# BOOST-IR.net
KiCad netlist of a schematic drawn in EAGLE
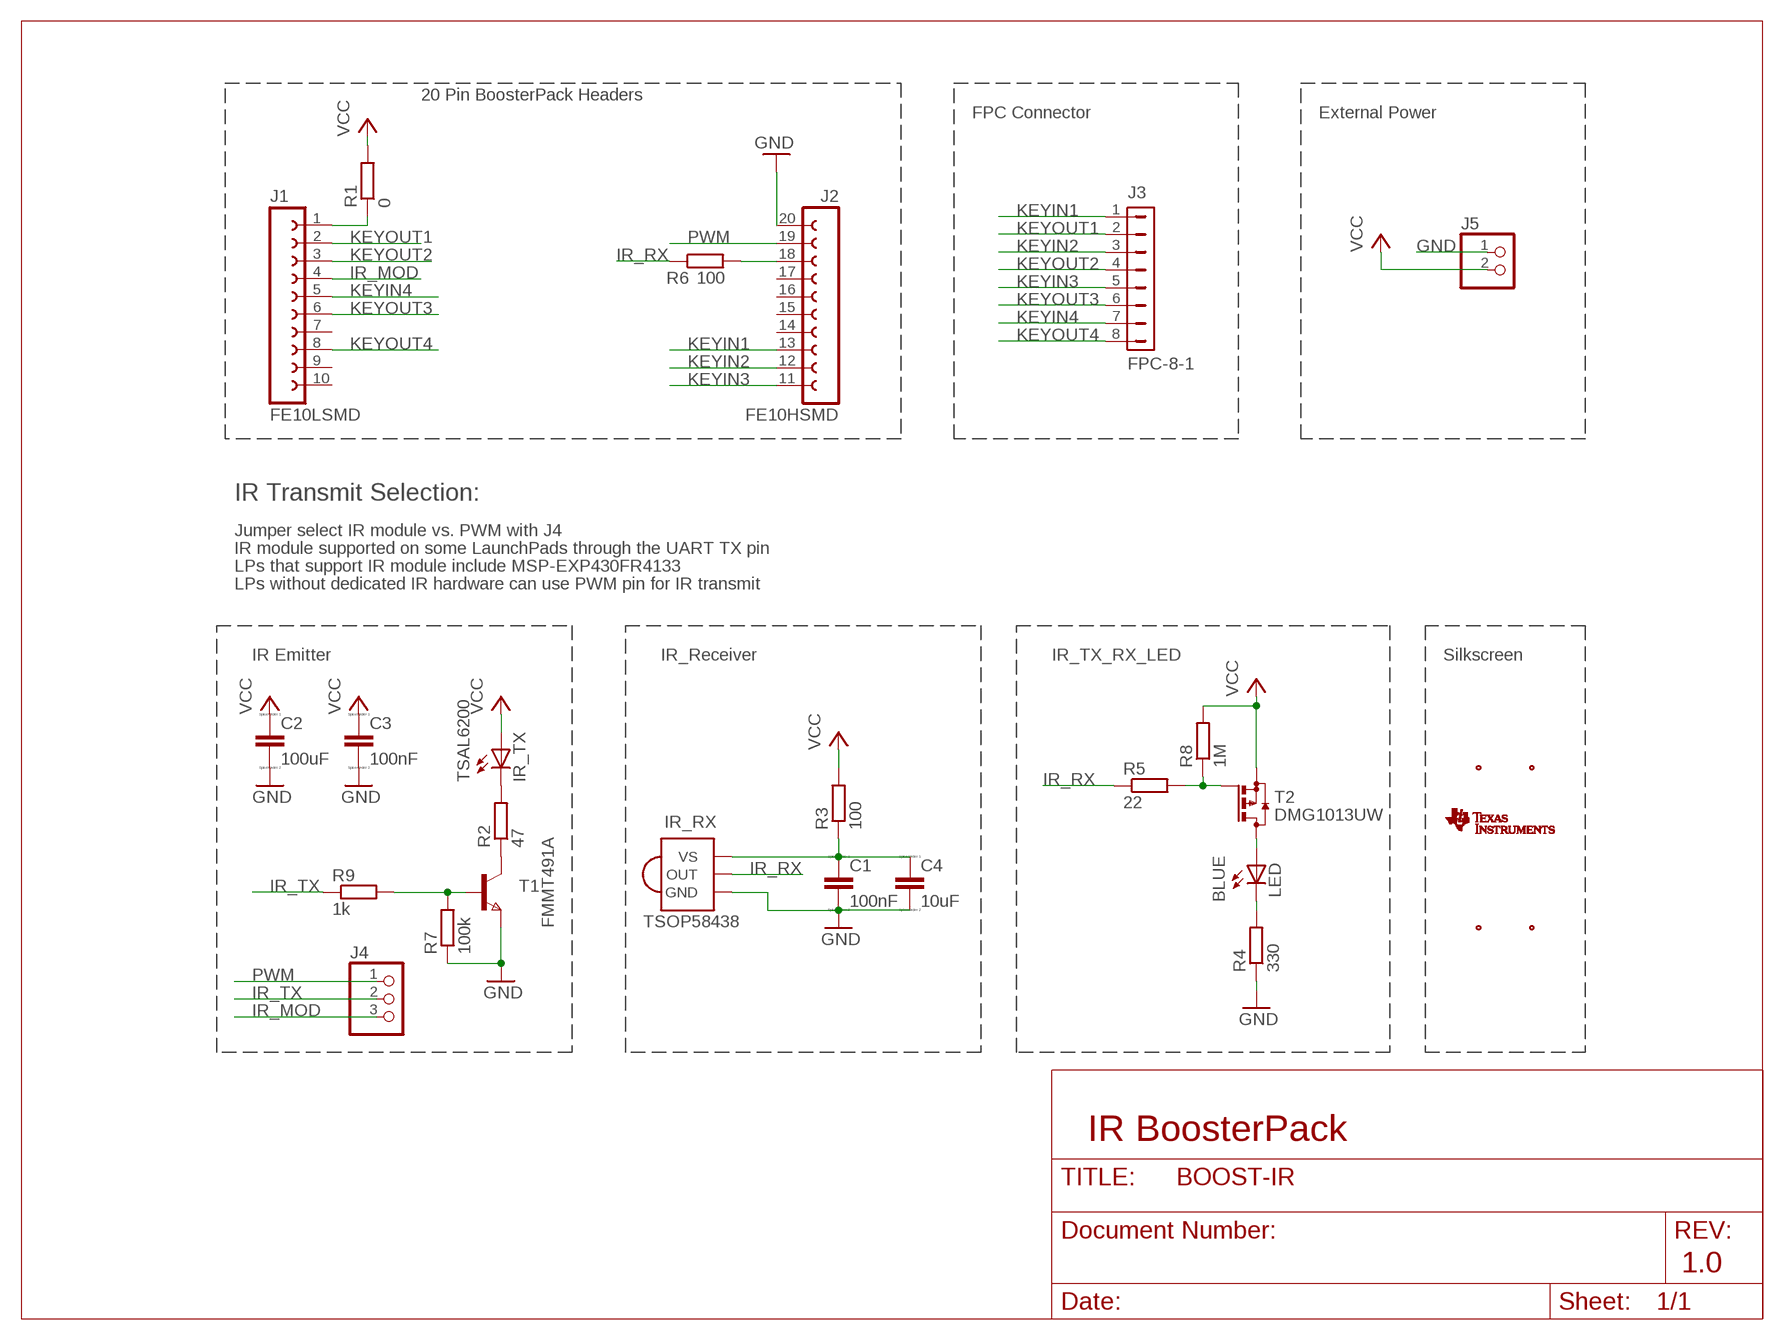
[diagram p0: schematic, sheet 1]

(export (version "E")
  (design (tool "Eeschema 10.0.6"))
  (components
    (comp (ref "C1")
      (value "100nF")
      (footprint "eagle-import:C0603")
      (libsource (lib "eagle-import") (part "CC0603"))
    )
    (comp (ref "C2")
      (value "100uF")
      (footprint "eagle-import:C1206")
      (libsource (lib "eagle-import") (part "CC1206"))
    )
    (comp (ref "C3")
      (value "100nF")
      (footprint "eagle-import:C0603")
      (libsource (lib "eagle-import") (part "CC0603"))
    )
    (comp (ref "C4")
      (value "10uF")
      (footprint "eagle-import:C0805")
      (libsource (lib "eagle-import") (part "C"))
    )
    (comp (ref "IR_RX")
      (value "TSOP58438")
      (footprint "eagle-import:TSOP58438")
      (libsource (lib "eagle-import") (part "TSOP58438"))
    )
    (comp (ref "IR_TX")
      (value "TSAL6200")
      (footprint "eagle-import:IR_LED_PAC")
      (libsource (lib "eagle-import") (part "IR_LED"))
    )
    (comp (ref "J1")
      (value "FE10LSMD")
      (footprint "eagle-import:FE10SMD")
      (libsource (lib "eagle-import") (part "FE10LSMD"))
    )
    (comp (ref "J2")
      (value "FE10HSMD")
      (footprint "eagle-import:FE10HSMD")
      (libsource (lib "eagle-import") (part "FE10HSMD"))
    )
    (comp (ref "J3")
      (value "FPC-8-1")
      (footprint "eagle-import:FPC_IR")
      (libsource (lib "eagle-import") (part "FPC_BP"))
    )
    (comp (ref "J4")
      (value "PINHD1X3")
      (footprint "eagle-import:1X03")
      (libsource (lib "eagle-import") (part "PINHD1X3"))
    )
    (comp (ref "J5")
      (value "HEADER1X2")
      (footprint "eagle-import:HEADER1X2")
      (libsource (lib "eagle-import") (part "HEADER1X2"))
    )
    (comp (ref "LED")
      (value "BLUE")
      (footprint "eagle-import:CHIPLED_0603")
      (libsource (lib "eagle-import") (part "LEDCHIPLED_0603"))
    )
    (comp (ref "R1")
      (value "0")
      (footprint "eagle-import:R1206")
      (libsource (lib "eagle-import") (part "R-EU_R1206"))
    )
    (comp (ref "R2")
      (value "47")
      (footprint "eagle-import:R1206")
      (libsource (lib "eagle-import") (part "R-EU_R1206"))
    )
    (comp (ref "R3")
      (value "100")
      (footprint "eagle-import:R0603")
      (libsource (lib "eagle-import") (part "R-EU_R0603"))
    )
    (comp (ref "R4")
      (value "330")
      (footprint "eagle-import:R0603")
      (libsource (lib "eagle-import") (part "R-EU_R0603"))
    )
    (comp (ref "R5")
      (value "22")
      (footprint "eagle-import:R0603")
      (libsource (lib "eagle-import") (part "R-EU_R0603"))
    )
    (comp (ref "R6")
      (value "100")
      (footprint "eagle-import:R0603")
      (libsource (lib "eagle-import") (part "R-EU_R0603"))
    )
    (comp (ref "R7")
      (value "100k")
      (footprint "eagle-import:R0603")
      (libsource (lib "eagle-import") (part "R-EU_R0603"))
    )
    (comp (ref "R8")
      (value "1M")
      (footprint "eagle-import:R0603")
      (libsource (lib "eagle-import") (part "R-EU_R0603"))
    )
    (comp (ref "R9")
      (value "1k")
      (footprint "eagle-import:R0603")
      (libsource (lib "eagle-import") (part "R-EU_R0603"))
    )
    (comp (ref "T1")
      (value "FMMT491A")
      (footprint "eagle-import:SOT-23")
      (fields (field (name "MPN") "DSS20201L-7"))
      (libsource (lib "eagle-import") (part "NPNSOT23"))
    )
    (comp (ref "T2")
      (value "DMG1013UW")
      (footprint "eagle-import:SOT323")
      (libsource (lib "eagle-import") (part "DMG1013UW"))
    )
    (comp (ref "U$1")
      (value "BOOST-IR_EXTPOWER")
      (footprint "eagle-import:BOOST-IR_EXTPOWER")
      (libsource (lib "eagle-import") (part "BOOST-IR_EXTPOWER"))
    )
    (comp (ref "U$3")
      (value "TI_LOGO_LETTERS")
      (footprint "eagle-import:TI_LOGO_WORDS")
      (libsource (lib "eagle-import") (part "TI_LOGO_LETTERS"))
    )
    (comp (ref "U$4")
      (value "BOOST-IR_LABEL")
      (footprint "eagle-import:BOOST-IR_LABEL")
      (libsource (lib "eagle-import") (part "BOOST-IR_LABEL"))
    )
    (comp (ref "U$5")
      (value "BOOST-IR_REV0.1LOGO")
      (footprint "eagle-import:BOOST-IR_LOGO")
      (libsource (lib "eagle-import") (part "BOOST-IR_REV0.1LOGO"))
    )
    (comp (ref "U$6")
      (value "BOOST-IR_REV0.1LOGOSMALL")
      (footprint "eagle-import:BOOST-IR_LOGOSMALL")
      (libsource (lib "eagle-import") (part "BOOST-IR_REV0.1LOGOSMALL"))
    )
  )
  (nets
    (net (code "1") (name "/IR_MOD") (class "Default")
      (node (ref "J1") (pin "4") (pinfunction "7_4") (pintype "passive"))
      (node (ref "J4") (pin "3") (pinfunction "3_3") (pintype "passive"))
    )
    (net (code "2") (name "/IR_RX") (class "Default")
      (node (ref "IR_RX") (pin "OUT") (pinfunction "OUT_OUT") (pintype "output"))
      (node (ref "R5") (pin "1") (pinfunction "1_1") (pintype "passive"))
      (node (ref "R6") (pin "1") (pinfunction "1_1") (pintype "passive"))
    )
    (net (code "3") (name "/IR_TX") (class "Default")
      (node (ref "J4") (pin "2") (pinfunction "2_2") (pintype "passive"))
      (node (ref "R9") (pin "1") (pinfunction "1_1") (pintype "passive"))
    )
    (net (code "4") (name "/KEYIN1") (class "Default")
      (node (ref "J2") (pin "13") (pinfunction "3_13") (pintype "passive"))
      (node (ref "J3") (pin "1") (pinfunction "1_1") (pintype "passive"))
    )
    (net (code "5") (name "/KEYIN2") (class "Default")
      (node (ref "J2") (pin "12") (pinfunction "2_12") (pintype "passive"))
      (node (ref "J3") (pin "3") (pinfunction "3_3") (pintype "passive"))
    )
    (net (code "6") (name "/KEYIN3") (class "Default")
      (node (ref "J2") (pin "11") (pinfunction "1_11") (pintype "passive"))
      (node (ref "J3") (pin "5") (pinfunction "5_5") (pintype "passive"))
    )
    (net (code "7") (name "/KEYIN4") (class "Default")
      (node (ref "J1") (pin "5") (pinfunction "6_5") (pintype "passive"))
      (node (ref "J3") (pin "7") (pinfunction "7_7") (pintype "passive"))
    )
    (net (code "8") (name "/KEYOUT1") (class "Default")
      (node (ref "J1") (pin "2") (pinfunction "9_2") (pintype "passive"))
      (node (ref "J3") (pin "2") (pinfunction "2_2") (pintype "passive"))
    )
    (net (code "9") (name "/KEYOUT2") (class "Default")
      (node (ref "J1") (pin "3") (pinfunction "8_3") (pintype "passive"))
      (node (ref "J3") (pin "4") (pinfunction "4_4") (pintype "passive"))
    )
    (net (code "10") (name "/KEYOUT3") (class "Default")
      (node (ref "J1") (pin "6") (pinfunction "5_6") (pintype "passive"))
      (node (ref "J3") (pin "6") (pinfunction "6_6") (pintype "passive"))
    )
    (net (code "11") (name "/KEYOUT4") (class "Default")
      (node (ref "J1") (pin "8") (pinfunction "3_8") (pintype "passive"))
      (node (ref "J3") (pin "8") (pinfunction "8_8") (pintype "passive"))
    )
    (net (code "12") (name "/PWM") (class "Default")
      (node (ref "J2") (pin "19") (pinfunction "9_19") (pintype "passive"))
      (node (ref "J4") (pin "1") (pinfunction "1_1") (pintype "passive"))
    )
    (net (code "13") (name "GND") (class "Default")
      (node (ref "C1") (pin "2") (pinfunction "2_2") (pintype "passive"))
      (node (ref "C2") (pin "2") (pinfunction "2_2") (pintype "passive"))
      (node (ref "C3") (pin "2") (pinfunction "2_2") (pintype "passive"))
      (node (ref "C4") (pin "2") (pinfunction "2_2") (pintype "passive"))
      (node (ref "IR_RX") (pin "GND") (pinfunction "GND_GND") (pintype "input"))
      (node (ref "J2") (pin "20") (pinfunction "10_20") (pintype "passive"))
      (node (ref "J5") (pin "1") (pinfunction "1_1") (pintype "passive"))
      (node (ref "R4") (pin "1") (pinfunction "1_1") (pintype "passive"))
      (node (ref "R7") (pin "1") (pinfunction "1_1") (pintype "passive"))
      (node (ref "T1") (pin "2") (pinfunction "E_2") (pintype "passive"))
    )
    (net (code "14") (name "Net-(C1-Pad1)") (class "Default")
      (node (ref "C1") (pin "1") (pinfunction "1_1") (pintype "passive"))
      (node (ref "C4") (pin "1") (pinfunction "1_1") (pintype "passive"))
      (node (ref "IR_RX") (pin "VS") (pinfunction "VS_VS") (pintype "input"))
      (node (ref "R3") (pin "1") (pinfunction "1_1") (pintype "passive"))
    )
    (net (code "15") (name "Net-(IR_TX-C)") (class "Default")
      (node (ref "IR_TX") (pin "K") (pinfunction "C_K") (pintype "passive"))
      (node (ref "R2") (pin "2") (pinfunction "2_2") (pintype "passive"))
    )
    (net (code "16") (name "Net-(J1-10)") (class "Default")
      (node (ref "J1") (pin "1") (pinfunction "10_1") (pintype "passive"))
      (node (ref "R1") (pin "1") (pinfunction "1_1") (pintype "passive"))
    )
    (net (code "17") (name "Net-(J2-8)") (class "Default")
      (node (ref "J2") (pin "18") (pinfunction "8_18") (pintype "passive"))
      (node (ref "R6") (pin "2") (pinfunction "2_2") (pintype "passive"))
    )
    (net (code "18") (name "Net-(LED-PadC)") (class "Default")
      (node (ref "LED") (pin "C") (pinfunction "C_C") (pintype "passive"))
      (node (ref "R4") (pin "2") (pinfunction "2_2") (pintype "passive"))
    )
    (net (code "19") (name "Net-(T1-B)") (class "Default")
      (node (ref "R7") (pin "2") (pinfunction "2_2") (pintype "passive"))
      (node (ref "R9") (pin "2") (pinfunction "2_2") (pintype "passive"))
      (node (ref "T1") (pin "3") (pinfunction "B_3") (pintype "passive"))
    )
    (net (code "20") (name "Net-(T1-C)") (class "Default")
      (node (ref "R2") (pin "1") (pinfunction "1_1") (pintype "passive"))
      (node (ref "T1") (pin "1") (pinfunction "C_1") (pintype "passive"))
    )
    (net (code "21") (name "Net-(T2-D)") (class "Default")
      (node (ref "LED") (pin "A") (pinfunction "A_A") (pintype "passive"))
      (node (ref "T2") (pin "3") (pinfunction "D_3") (pintype "passive"))
    )
    (net (code "22") (name "Net-(T2-G)") (class "Default")
      (node (ref "R5") (pin "2") (pinfunction "2_2") (pintype "passive"))
      (node (ref "R8") (pin "1") (pinfunction "1_1") (pintype "passive"))
      (node (ref "T2") (pin "1") (pinfunction "G_1") (pintype "passive"))
    )
    (net (code "23") (name "VCC") (class "Default")
      (node (ref "C2") (pin "1") (pinfunction "1_1") (pintype "passive"))
      (node (ref "C3") (pin "1") (pinfunction "1_1") (pintype "passive"))
      (node (ref "IR_TX") (pin "A") (pinfunction "A_A") (pintype "passive"))
      (node (ref "J5") (pin "2") (pinfunction "2_2") (pintype "passive"))
      (node (ref "R1") (pin "2") (pinfunction "2_2") (pintype "passive"))
      (node (ref "R3") (pin "2") (pinfunction "2_2") (pintype "passive"))
      (node (ref "R8") (pin "2") (pinfunction "2_2") (pintype "passive"))
      (node (ref "T2") (pin "2") (pinfunction "S_2") (pintype "passive"))
    )
    (net (code "24") (name "unconnected-(J1-1-Pad10)") (class "Default")
      (node (ref "J1") (pin "10") (pinfunction "1_10") (pintype "passive"))
    )
    (net (code "25") (name "unconnected-(J1-2-Pad9)") (class "Default")
      (node (ref "J1") (pin "9") (pinfunction "2_9") (pintype "passive"))
    )
    (net (code "26") (name "unconnected-(J1-4-Pad7)") (class "Default")
      (node (ref "J1") (pin "7") (pinfunction "4_7") (pintype "passive"))
    )
    (net (code "27") (name "unconnected-(J2-4-Pad14)") (class "Default")
      (node (ref "J2") (pin "14") (pinfunction "4_14") (pintype "passive"))
    )
    (net (code "28") (name "unconnected-(J2-5-Pad15)") (class "Default")
      (node (ref "J2") (pin "15") (pinfunction "5_15") (pintype "passive"))
    )
    (net (code "29") (name "unconnected-(J2-6-Pad16)") (class "Default")
      (node (ref "J2") (pin "16") (pinfunction "6_16") (pintype "passive"))
    )
    (net (code "30") (name "unconnected-(J2-7-Pad17)") (class "Default")
      (node (ref "J2") (pin "17") (pinfunction "7_17") (pintype "passive"))
    )
  )
)
